# System_PMU_for_RK3399.net
KiCad netlist of a schematic drawn in Altium Designer
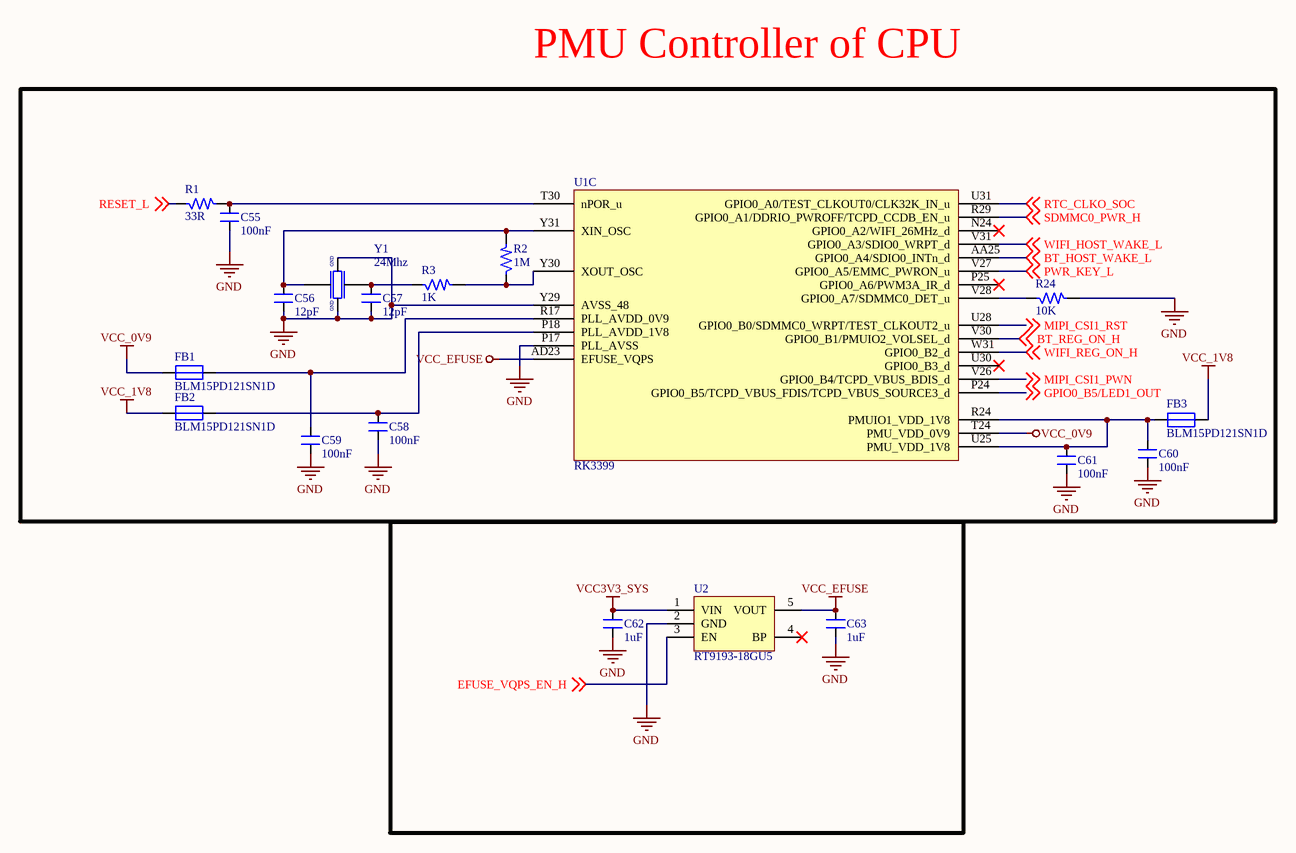
[diagram p0: System PMU for RK3399.SchDoc]

(export (version "E")
  (design (tool "Eeschema 10.0.6"))
  (components
    (comp (ref "C55")
      (value "100nF")
      (footprint "CAP_0201")
      (description "0.1µF ±10% 25V Ceramic Capacitor X5R 0201 (0603 Metric)")
      (fields
        (field (name "MANUFACTURER") "TDK Corporation")
        (field (name "MANUFACTURER PART NUMBER") "C0603X5R1E104K030BB")
      )
      (libsource (lib "RK3399 _Module_Intlib") (part "CAP_100nF-25V-10%-0201"))
    )
    (comp (ref "C56")
      (value "12pF")
      (footprint "CAP_0201")
      (description "12pF ±10% 16V Ceramic Capacitor C0G, NP0 0201 (0603 Metric)")
      (fields
        (field (name "MANUFACTURER") "AVX Corporation")
        (field (name "MANUFACTURER PART NUMBER") "0201YA120KAT2A")
      )
      (libsource (lib "RK3399 _Module_Intlib") (part "CAP_12pF-16V-10%-0201"))
    )
    (comp (ref "C57")
      (value "12pF")
      (footprint "CAP_0201")
      (description "12pF ±10% 16V Ceramic Capacitor C0G, NP0 0201 (0603 Metric)")
      (fields
        (field (name "MANUFACTURER") "AVX Corporation")
        (field (name "MANUFACTURER PART NUMBER") "0201YA120KAT2A")
      )
      (libsource (lib "RK3399 _Module_Intlib") (part "CAP_12pF-16V-10%-0201"))
    )
    (comp (ref "C58")
      (value "100nF")
      (footprint "CAP_0201")
      (description "0.1µF ±10% 25V Ceramic Capacitor X5R 0201 (0603 Metric)")
      (fields
        (field (name "MANUFACTURER") "TDK Corporation")
        (field (name "MANUFACTURER PART NUMBER") "C0603X5R1E104K030BB")
      )
      (libsource (lib "RK3399 _Module_Intlib") (part "CAP_100nF-25V-10%-0201"))
    )
    (comp (ref "C59")
      (value "100nF")
      (footprint "CAP_0201")
      (description "0.1µF ±10% 25V Ceramic Capacitor X5R 0201 (0603 Metric)")
      (fields
        (field (name "MANUFACTURER") "TDK Corporation")
        (field (name "MANUFACTURER PART NUMBER") "C0603X5R1E104K030BB")
      )
      (libsource (lib "RK3399 _Module_Intlib") (part "CAP_100nF-25V-10%-0201"))
    )
    (comp (ref "C60")
      (value "100nF")
      (footprint "CAP_0201")
      (description "0.1µF ±10% 25V Ceramic Capacitor X5R 0201 (0603 Metric)")
      (fields
        (field (name "MANUFACTURER") "TDK Corporation")
        (field (name "MANUFACTURER PART NUMBER") "C0603X5R1E104K030BB")
      )
      (libsource (lib "RK3399 _Module_Intlib") (part "CAP_100nF-25V-10%-0201"))
    )
    (comp (ref "C61")
      (value "100nF")
      (footprint "CAP_0201")
      (description "0.1µF ±10% 25V Ceramic Capacitor X5R 0201 (0603 Metric)")
      (fields
        (field (name "MANUFACTURER") "TDK Corporation")
        (field (name "MANUFACTURER PART NUMBER") "C0603X5R1E104K030BB")
      )
      (libsource (lib "RK3399 _Module_Intlib") (part "CAP_100nF-25V-10%-0201"))
    )
    (comp (ref "C62")
      (value "1uF")
      (footprint "CAP_0201")
      (description "1µF ±20% 16V Ceramic Capacitor X5R 0201 (0603 Metric)")
      (fields
        (field (name "MANUFACTURER") "Samsung Electro-Mechanics")
        (field (name "MANUFACTURER PART NUMBER") "CL03A105MO3NRNH")
      )
      (libsource (lib "RK3399 _Module_Intlib") (part "CAP_1uF-16V-10%-0201"))
    )
    (comp (ref "C63")
      (value "1uF")
      (footprint "CAP_0201")
      (description "1µF ±20% 16V Ceramic Capacitor X5R 0201 (0603 Metric)")
      (fields
        (field (name "MANUFACTURER") "Samsung Electro-Mechanics")
        (field (name "MANUFACTURER PART NUMBER") "CL03A105MO3NRNH")
      )
      (libsource (lib "RK3399 _Module_Intlib") (part "CAP_1uF-16V-10%-0201"))
    )
    (comp (ref "FB1")
      (value "BLM15PD121SN1D")
      (footprint "RES_0402")
      (description "120 Ohms @ 100MHz 1 Power Line Ferrite Bead 0402 (1005 Metric) 1.3A 90mOhm")
      (fields (field (name "MANUFACTURER") "Murata Electronics"))
      (libsource (lib "RK3399 _Module_Schlib") (part "FB_120R-1.3A-100Mhz-0402"))
    )
    (comp (ref "FB2")
      (value "BLM15PD121SN1D")
      (footprint "RES_0402")
      (description "120 Ohms @ 100MHz 1 Power Line Ferrite Bead 0402 (1005 Metric) 1.3A 90mOhm")
      (fields (field (name "MANUFACTURER") "Murata Electronics"))
      (libsource (lib "RK3399 _Module_Schlib") (part "FB_120R-1.3A-100Mhz-0402"))
    )
    (comp (ref "FB3")
      (value "BLM15PD121SN1D")
      (footprint "RES_0402")
      (description "120 Ohms @ 100MHz 1 Power Line Ferrite Bead 0402 (1005 Metric) 1.3A 90mOhm")
      (fields (field (name "MANUFACTURER") "Murata Electronics"))
      (libsource (lib "RK3399 _Module_Schlib") (part "FB_120R-1.3A-100Mhz-0402"))
    )
    (comp (ref "R1")
      (value "33R")
      (footprint "RES_0201")
      (description "33 Ohms ±1% 0.05W, 1/20W Chip Resistor 0201 (0603 Metric) Thick Film")
      (fields
        (field (name "MANUFACTURER") "Yageo")
        (field (name "MANUFACTURER PART NUMBER") "RC0201FR-0733RL")
      )
      (libsource (lib "RK3399 _Module_Intlib") (part "RES_33R-0.05W-1%-0201"))
    )
    (comp (ref "R2")
      (value "1M")
      (footprint "RES_0201")
      (description "1 MOhms ±1% 0.05W, 1/20W Chip Resistor 0201 (0603 Metric) Thick Film")
      (fields
        (field (name "MANUFACTURER") "Yageo")
        (field (name "MANUFACTURER PART NUMBER") "RC0201FR-071ML")
      )
      (libsource (lib "RK3399 _Module_Intlib") (part "RES_1M-0.05W-1%-0201"))
    )
    (comp (ref "R3")
      (value "1K")
      (footprint "RES_0201")
      (description "1 kOhms ±1% 0.05W, 1/20W Chip Resistor 0201 (0603 Metric) Thick Film")
      (fields
        (field (name "MANUFACTURER") "Yageo")
        (field (name "MANUFACTURER PART NUMBER") "RC0201FR-071KL")
      )
      (libsource (lib "RK3399 _Module_Intlib") (part "RES_1K-0.05W-1%-0201"))
    )
    (comp (ref "R24")
      (value "10K")
      (footprint "RES_0201")
      (description "10 kOhms ±1% 0.05W, 1/20W Chip Resistor 0201 (0603 Metric) Thick Film")
      (fields
        (field (name "MANUFACTURER") "Stackpole Electronics Inc")
        (field (name "MANUFACTURER PART NUMBER") "RMCF0201FT10K0")
      )
      (libsource (lib "EsteemPCB_COB_Course_intlib") (part "RES_10K-0.05W-1%-0201"))
    )
    (comp (ref "U1")
      (value "RK3399")
      (footprint "FBGA828_23_826X826")
      (description "RK3399 is a low power, high performance processor for computing, personal mobile.")
      (fields (field (name "MANUFACTURER") "Rockchip"))
      (libsource (lib "RK3399 _Module_Schlib") (part "IC_RK3399-FCBGA828"))
    )
    (comp (ref "U2")
      (value "RT9193-18GU5")
      (footprint "SC70-5")
      (description "Linear Voltage Regulator IC 1 Output 300mA SC-70-5")
      (fields (field (name "MANUFACTURER") "Richtek USA Inc."))
      (libsource (lib "RK3399 _Module_Schlib") (part "REG_1.8V-300mA-5.5V-SC70-5"))
    )
    (comp (ref "Y1")
      (value "24Mhz")
      (footprint "XTAL_ABM8AIG-24.000MHZ-12-2Z-T3")
      (description "24MHz ±20ppm Crystal 12pF 50 Ohms 4-SMD, No Lead")
      (fields
        (field (name "MANUFACTURER") "Abracon LLC")
        (field (name "MANUFACTURER PART NUMBER") "ABM8AIG-24.000MHZ-12-2Z-T3")
      )
      (libsource (lib "RK3399 _Module_Schlib") (part "XTAL_24Mhz-12pF-4-SMD"))
    )
  )
  (nets
    (net (code "1") (name "BT_HOST_WAKE_L") (class "Default")
      (node (ref "U1") (pin "AA25") (pinfunction "GPIO0_A4/SDIO0_INTn_d_AA25") (pintype "passive"))
    )
    (net (code "2") (name "BT_REG_ON_H") (class "Default")
      (node (ref "U1") (pin "V30") (pinfunction "GPIO0_B1/PMUIO2_VOLSEL_d_V30") (pintype "passive"))
    )
    (net (code "3") (name "EFUSE_VQPS_EN_H") (class "Default")
      (node (ref "U2") (pin "3") (pinfunction "EN_3") (pintype "passive"))
    )
    (net (code "4") (name "GND") (class "Default")
      (node (ref "C55") (pin "1") (pinfunction "1_1") (pintype "passive"))
      (node (ref "C56") (pin "1") (pinfunction "1_1") (pintype "passive"))
      (node (ref "C57") (pin "1") (pinfunction "1_1") (pintype "passive"))
      (node (ref "C58") (pin "1") (pinfunction "1_1") (pintype "passive"))
      (node (ref "C59") (pin "1") (pinfunction "1_1") (pintype "passive"))
      (node (ref "C60") (pin "1") (pinfunction "1_1") (pintype "passive"))
      (node (ref "C61") (pin "1") (pinfunction "1_1") (pintype "passive"))
      (node (ref "C62") (pin "1") (pinfunction "1_1") (pintype "passive"))
      (node (ref "C63") (pin "1") (pinfunction "1_1") (pintype "passive"))
      (node (ref "R24") (pin "2") (pinfunction "2_2") (pintype "passive"))
      (node (ref "U1") (pin "P17") (pinfunction "PLL_AVSS_P17") (pintype "passive"))
      (node (ref "U1") (pin "Y29") (pinfunction "AVSS_48_Y29") (pintype "passive"))
      (node (ref "U2") (pin "2") (pinfunction "GND_2") (pintype "passive"))
      (node (ref "Y1") (pin "2") (pinfunction "2_2") (pintype "passive"))
      (node (ref "Y1") (pin "4") (pinfunction "4_4") (pintype "passive"))
    )
    (net (code "5") (name "GPIO0_B5{slash}LED1_OUT") (class "Default")
      (node (ref "U1") (pin "P24") (pinfunction "GPIO0_B5/TCPD_VBUS_FDIS/TCPD_VBUS_SOURCE3_d_P24") (pintype "passive"))
    )
    (net (code "6") (name "MIPI_CSI1_PWN") (class "Default")
      (node (ref "U1") (pin "V26") (pinfunction "GPIO0_B4/TCPD_VBUS_BDIS_d_V26") (pintype "passive"))
    )
    (net (code "7") (name "MIPI_CSI1_RST") (class "Default")
      (node (ref "U1") (pin "U28") (pinfunction "GPIO0_B0/SDMMC0_WRPT/TEST_CLKOUT2_u_U28") (pintype "passive"))
    )
    (net (code "8") (name "Net-(C57-Pad2)") (class "Default")
      (node (ref "C57") (pin "2") (pinfunction "2_2") (pintype "passive"))
      (node (ref "R3") (pin "1") (pinfunction "1_1") (pintype "passive"))
      (node (ref "Y1") (pin "3") (pinfunction "3_3") (pintype "passive"))
    )
    (net (code "9") (name "Net-(U1C-GPIO0_A7{slash}SDMMC0_DET_u)") (class "Default")
      (node (ref "R24") (pin "1") (pinfunction "1_1") (pintype "passive"))
      (node (ref "U1") (pin "V28") (pinfunction "GPIO0_A7/SDMMC0_DET_u_V28") (pintype "passive"))
    )
    (net (code "10") (name "Net-(U1C-PLL_AVDD_0V9)") (class "Default")
      (node (ref "C59") (pin "2") (pinfunction "2_2") (pintype "passive"))
      (node (ref "FB1") (pin "2") (pinfunction "2_2") (pintype "passive"))
      (node (ref "U1") (pin "R17") (pinfunction "PLL_AVDD_0V9_R17") (pintype "passive"))
    )
    (net (code "11") (name "Net-(U1C-PLL_AVDD_1V8)") (class "Default")
      (node (ref "C58") (pin "2") (pinfunction "2_2") (pintype "passive"))
      (node (ref "FB2") (pin "2") (pinfunction "2_2") (pintype "passive"))
      (node (ref "U1") (pin "P18") (pinfunction "PLL_AVDD_1V8_P18") (pintype "passive"))
    )
    (net (code "12") (name "Net-(U1C-PMUIO1_VDD_1V8)") (class "Default")
      (node (ref "C60") (pin "2") (pinfunction "2_2") (pintype "passive"))
      (node (ref "C61") (pin "2") (pinfunction "2_2") (pintype "passive"))
      (node (ref "FB3") (pin "1") (pinfunction "1_1") (pintype "passive"))
      (node (ref "U1") (pin "R24") (pinfunction "PMUIO1_VDD_1V8_R24") (pintype "passive"))
      (node (ref "U1") (pin "U25") (pinfunction "PMU_VDD_1V8_U25") (pintype "passive"))
    )
    (net (code "13") (name "Net-(U1C-XIN_OSC)") (class "Default")
      (node (ref "C56") (pin "2") (pinfunction "2_2") (pintype "passive"))
      (node (ref "R2") (pin "2") (pinfunction "2_2") (pintype "passive"))
      (node (ref "U1") (pin "Y31") (pinfunction "XIN_OSC_Y31") (pintype "passive"))
      (node (ref "Y1") (pin "1") (pinfunction "1_1") (pintype "passive"))
    )
    (net (code "14") (name "Net-(U1C-XOUT_OSC)") (class "Default")
      (node (ref "R2") (pin "1") (pinfunction "1_1") (pintype "passive"))
      (node (ref "R3") (pin "2") (pinfunction "2_2") (pintype "passive"))
      (node (ref "U1") (pin "Y30") (pinfunction "XOUT_OSC_Y30") (pintype "passive"))
    )
    (net (code "15") (name "Net-(U1C-nPOR_u)") (class "Default")
      (node (ref "C55") (pin "2") (pinfunction "2_2") (pintype "passive"))
      (node (ref "R1") (pin "2") (pinfunction "2_2") (pintype "passive"))
      (node (ref "U1") (pin "T30") (pinfunction "nPOR_u_T30") (pintype "passive"))
    )
    (net (code "16") (name "PWR_KEY_L") (class "Default")
      (node (ref "U1") (pin "V27") (pinfunction "GPIO0_A5/EMMC_PWRON_u_V27") (pintype "passive"))
    )
    (net (code "17") (name "RESET_L") (class "Default")
      (node (ref "R1") (pin "1") (pinfunction "1_1") (pintype "passive"))
    )
    (net (code "18") (name "RTC_CLKO_SOC") (class "Default")
      (node (ref "U1") (pin "U31") (pinfunction "GPIO0_A0/TEST_CLKOUT0/CLK32K_IN_u_U31") (pintype "passive"))
    )
    (net (code "19") (name "SDMMC0_PWR_H") (class "Default")
      (node (ref "U1") (pin "R29") (pinfunction "GPIO0_A1/DDRIO_PWROFF/TCPD_CCDB_EN_u_R29") (pintype "passive"))
    )
    (net (code "20") (name "VCC3V3_SYS") (class "Default")
      (node (ref "C62") (pin "2") (pinfunction "2_2") (pintype "passive"))
      (node (ref "U2") (pin "1") (pinfunction "VIN_1") (pintype "passive"))
    )
    (net (code "21") (name "VCC_0V9") (class "Default")
      (node (ref "FB1") (pin "1") (pinfunction "1_1") (pintype "passive"))
      (node (ref "U1") (pin "T24") (pinfunction "PMU_VDD_0V9_T24") (pintype "passive"))
    )
    (net (code "22") (name "VCC_1V8") (class "Default")
      (node (ref "FB2") (pin "1") (pinfunction "1_1") (pintype "passive"))
      (node (ref "FB3") (pin "2") (pinfunction "2_2") (pintype "passive"))
    )
    (net (code "23") (name "VCC_EFUSE") (class "Default")
      (node (ref "C63") (pin "2") (pinfunction "2_2") (pintype "passive"))
      (node (ref "U1") (pin "AD23") (pinfunction "EFUSE_VQPS_AD23") (pintype "passive"))
      (node (ref "U2") (pin "5") (pinfunction "VOUT_5") (pintype "passive"))
    )
    (net (code "24") (name "WIFI_HOST_WAKE_L") (class "Default")
      (node (ref "U1") (pin "V31") (pinfunction "GPIO0_A3/SDIO0_WRPT_d_V31") (pintype "passive"))
    )
    (net (code "25") (name "WIFI_REG_ON_H") (class "Default")
      (node (ref "U1") (pin "W31") (pinfunction "GPIO0_B2_d_W31") (pintype "passive"))
    )
    (net (code "26") (name "unconnected-(U1C-GPIO0_A2{slash}WIFI_26MHz_d-PadN24)") (class "Default")
      (node (ref "U1") (pin "N24") (pinfunction "GPIO0_A2/WIFI_26MHz_d_N24") (pintype "passive+no_connect"))
    )
    (net (code "27") (name "unconnected-(U1C-GPIO0_A6{slash}PWM3A_IR_d-PadP25)") (class "Default")
      (node (ref "U1") (pin "P25") (pinfunction "GPIO0_A6/PWM3A_IR_d_P25") (pintype "passive+no_connect"))
    )
    (net (code "28") (name "unconnected-(U1C-GPIO0_B3_d-PadU30)") (class "Default")
      (node (ref "U1") (pin "U30") (pinfunction "GPIO0_B3_d_U30") (pintype "passive+no_connect"))
    )
    (net (code "29") (name "unconnected-(U2-BP-Pad4)") (class "Default")
      (node (ref "U2") (pin "4") (pinfunction "BP_4") (pintype "passive+no_connect"))
    )
  )
)
